# section1.net
KiCad netlist of a schematic drawn in EasyEDA
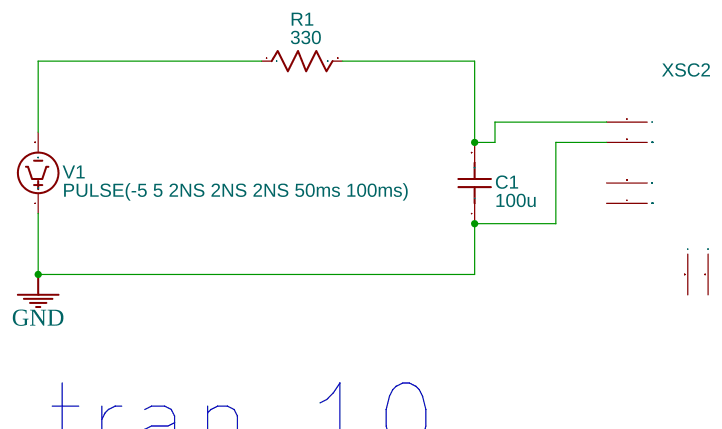
[diagram p0: schematic sheet]

(export (version "E")
  (design (tool "Eeschema 10.0.6"))
  (components
    (comp (ref "C1") (value "100u") (libsource (lib "") (part "Capacitor_US")))
    (comp (ref "R1") (value "330") (libsource (lib "") (part "Resistor_US")))
    (comp (ref "V1") (value "PULSE(-5 5 2NS 2NS 2NS 50ms 100ms)") (libsource (lib "") (part "VPULSE")))
    (comp (ref "XSC2") (value "Oscilloscope") (libsource (lib "") (part "OSCILLOSCOPE")))
  )
  (nets
    (net (code "1") (name "GND") (class "Default")
      (node (ref "C1") (pin "1") (pinfunction "1_1") (pintype "unspecified"))
      (node (ref "V1") (pin "1") (pinfunction "1_1") (pintype "unspecified"))
      (node (ref "XSC2") (pin "2") (pinfunction "GND1_2") (pintype "unspecified"))
    )
    (net (code "2") (name "Net-(R1-Pad1)") (class "Default")
      (node (ref "R1") (pin "1") (pinfunction "1_1") (pintype "unspecified"))
      (node (ref "V1") (pin "2") (pinfunction "2_2") (pintype "unspecified"))
    )
    (net (code "3") (name "Net-(XSC2-A)") (class "Default")
      (node (ref "C1") (pin "2") (pinfunction "2_2") (pintype "unspecified"))
      (node (ref "R1") (pin "2") (pinfunction "2_2") (pintype "unspecified"))
      (node (ref "XSC2") (pin "1") (pinfunction "A_1") (pintype "unspecified"))
    )
    (net (code "4") (name "unconnected-(XSC2-B-Pad3)") (class "Default")
      (node (ref "XSC2") (pin "3") (pinfunction "B_3") (pintype "unspecified"))
    )
    (net (code "5") (name "unconnected-(XSC2-GND2-Pad4)") (class "Default")
      (node (ref "XSC2") (pin "4") (pinfunction "GND2_4") (pintype "unspecified"))
    )
    (net (code "6") (name "unconnected-(XSC2-T+-Pad5)") (class "Default")
      (node (ref "XSC2") (pin "5") (pinfunction "T+_5") (pintype "unspecified"))
    )
    (net (code "7") (name "unconnected-(XSC2-T--Pad6)") (class "Default")
      (node (ref "XSC2") (pin "6") (pinfunction "T-_6") (pintype "unspecified"))
    )
  )
)
